# base_mcu_sch.net
KiCad netlist of a schematic drawn in EAGLE
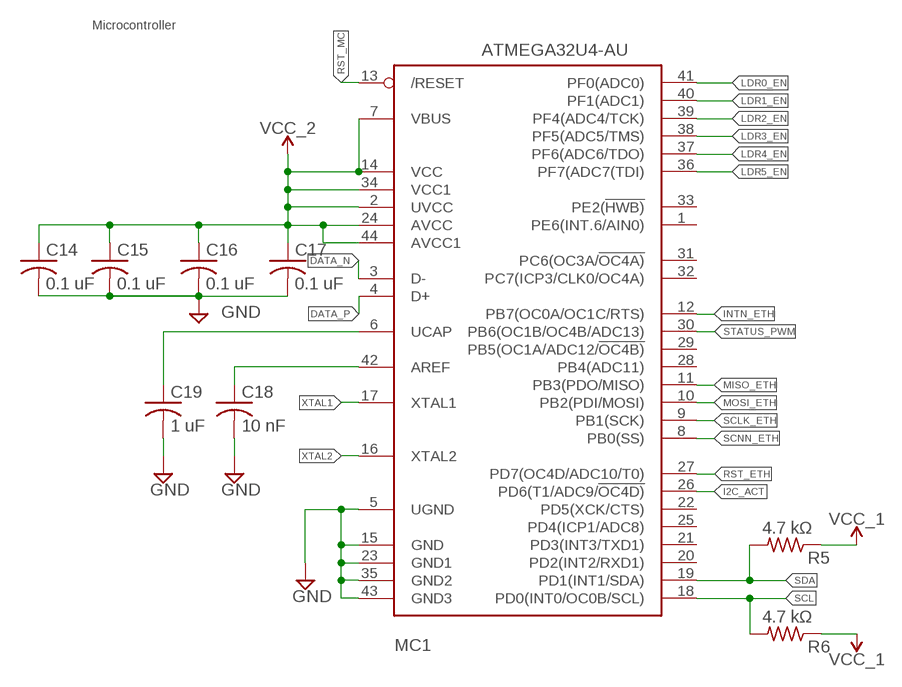
[diagram p0: schematic, sheet 1]

(export (version "E")
  (design (tool "Eeschema 10.0.6"))
  (components
    (comp (ref "C14")
      (value "0.1 uF")
      (footprint "eagle-import:C0603")
      (libsource (lib "eagle-import") (part "C-USC0603"))
    )
    (comp (ref "C15")
      (value "0.1 uF")
      (footprint "eagle-import:C0603")
      (libsource (lib "eagle-import") (part "C-USC0603"))
    )
    (comp (ref "C16")
      (value "0.1 uF")
      (footprint "eagle-import:C0603")
      (libsource (lib "eagle-import") (part "C-USC0603"))
    )
    (comp (ref "C17")
      (value "0.1 uF")
      (footprint "eagle-import:C0603")
      (libsource (lib "eagle-import") (part "C-USC0603"))
    )
    (comp (ref "C18")
      (value "10 nF")
      (footprint "eagle-import:C0603")
      (libsource (lib "eagle-import") (part "C-USC0603"))
    )
    (comp (ref "C19")
      (value "1 uF")
      (footprint "eagle-import:C0603")
      (libsource (lib "eagle-import") (part "C-USC0603"))
    )
    (comp (ref "MC1")
      (value "ATMEGA32U4-AU")
      (footprint "eagle-import:TQFP44")
      (libsource (lib "eagle-import") (part "ATMEGA32U4-AU"))
    )
    (comp (ref "R5")
      (value "4.7 kΩ")
      (footprint "eagle-import:R0603")
      (libsource (lib "eagle-import") (part "R-US_R0603"))
    )
    (comp (ref "R6")
      (value "4.7 kΩ")
      (footprint "eagle-import:R0603")
      (libsource (lib "eagle-import") (part "R-US_R0603"))
    )
  )
  (nets
    (net (code "1") (name "DATA_N") (class "Default")
      (node (ref "MC1") (pin "3") (pinfunction "D-_3") (pintype "bidirectional"))
    )
    (net (code "2") (name "DATA_P") (class "Default")
      (node (ref "MC1") (pin "4") (pinfunction "D+_4") (pintype "bidirectional"))
    )
    (net (code "3") (name "GND") (class "Default")
      (node (ref "C14") (pin "2") (pinfunction "2_2") (pintype "passive"))
      (node (ref "C15") (pin "2") (pinfunction "2_2") (pintype "passive"))
      (node (ref "C16") (pin "2") (pinfunction "2_2") (pintype "passive"))
      (node (ref "C17") (pin "2") (pinfunction "2_2") (pintype "passive"))
      (node (ref "C18") (pin "2") (pinfunction "2_2") (pintype "passive"))
      (node (ref "C19") (pin "2") (pinfunction "2_2") (pintype "passive"))
      (node (ref "MC1") (pin "15") (pinfunction "GND_15") (pintype "bidirectional"))
      (node (ref "MC1") (pin "23") (pinfunction "GND1_23") (pintype "bidirectional"))
      (node (ref "MC1") (pin "35") (pinfunction "GND2_35") (pintype "bidirectional"))
      (node (ref "MC1") (pin "43") (pinfunction "GND3_43") (pintype "bidirectional"))
      (node (ref "MC1") (pin "5") (pinfunction "UGND_5") (pintype "bidirectional"))
    )
    (net (code "4") (name "I2C_ACT") (class "Default")
      (node (ref "MC1") (pin "26") (pinfunction "PD6(T1/ADC9/~{OC4D})_26") (pintype "bidirectional"))
    )
    (net (code "5") (name "INTN_ETH") (class "Default")
      (node (ref "MC1") (pin "12") (pinfunction "PB7(OC0A/OC1C/RTS)_12") (pintype "bidirectional"))
    )
    (net (code "6") (name "LDR0_EN") (class "Default")
      (node (ref "MC1") (pin "41") (pinfunction "PF0(ADC0)_41") (pintype "bidirectional"))
    )
    (net (code "7") (name "LDR1_EN") (class "Default")
      (node (ref "MC1") (pin "40") (pinfunction "PF1(ADC1)_40") (pintype "bidirectional"))
    )
    (net (code "8") (name "LDR2_EN") (class "Default")
      (node (ref "MC1") (pin "39") (pinfunction "PF4(ADC4/TCK)_39") (pintype "bidirectional"))
    )
    (net (code "9") (name "LDR3_EN") (class "Default")
      (node (ref "MC1") (pin "38") (pinfunction "PF5(ADC5/TMS)_38") (pintype "bidirectional"))
    )
    (net (code "10") (name "LDR4_EN") (class "Default")
      (node (ref "MC1") (pin "37") (pinfunction "PF6(ADC6/TDO)_37") (pintype "bidirectional"))
    )
    (net (code "11") (name "LDR5_EN") (class "Default")
      (node (ref "MC1") (pin "36") (pinfunction "PF7(ADC7(TDI)_36") (pintype "bidirectional"))
    )
    (net (code "12") (name "MISO_ETH") (class "Default")
      (node (ref "MC1") (pin "11") (pinfunction "PB3(PDO/MISO)_11") (pintype "bidirectional"))
    )
    (net (code "13") (name "MOSI_ETH") (class "Default")
      (node (ref "MC1") (pin "10") (pinfunction "PB2(PDI/MOSI)_10") (pintype "bidirectional"))
    )
    (net (code "14") (name "Net-(MC1-AREF)") (class "Default")
      (node (ref "C18") (pin "1") (pinfunction "1_1") (pintype "passive"))
      (node (ref "MC1") (pin "42") (pinfunction "AREF_42") (pintype "bidirectional"))
    )
    (net (code "15") (name "Net-(MC1-UCAP)") (class "Default")
      (node (ref "C19") (pin "1") (pinfunction "1_1") (pintype "passive"))
      (node (ref "MC1") (pin "6") (pinfunction "UCAP_6") (pintype "bidirectional"))
    )
    (net (code "16") (name "RST_ETH") (class "Default")
      (node (ref "MC1") (pin "27") (pinfunction "PD7(OC4D/ADC10/T0)_27") (pintype "bidirectional"))
    )
    (net (code "17") (name "RST_MC") (class "Default")
      (node (ref "MC1") (pin "13") (pinfunction "/RESET_13") (pintype "bidirectional"))
    )
    (net (code "18") (name "SCL") (class "Default")
      (node (ref "MC1") (pin "18") (pinfunction "PD0(INT0/OC0B/SCL)_18") (pintype "bidirectional"))
      (node (ref "R6") (pin "2") (pinfunction "2_2") (pintype "passive"))
    )
    (net (code "19") (name "SCLK_ETH") (class "Default")
      (node (ref "MC1") (pin "9") (pinfunction "PB1(SCK)_9") (pintype "bidirectional"))
    )
    (net (code "20") (name "SCNN_ETH") (class "Default")
      (node (ref "MC1") (pin "8") (pinfunction "PB0(SS)_8") (pintype "bidirectional"))
    )
    (net (code "21") (name "SDA") (class "Default")
      (node (ref "MC1") (pin "19") (pinfunction "PD1(INT1/SDA)_19") (pintype "bidirectional"))
      (node (ref "R5") (pin "2") (pinfunction "2_2") (pintype "passive"))
    )
    (net (code "22") (name "STATUS_PWM") (class "Default")
      (node (ref "MC1") (pin "30") (pinfunction "PB6(OC1B/OC4B/ADC13)_30") (pintype "bidirectional"))
    )
    (net (code "23") (name "VCC_1") (class "Default")
      (node (ref "R5") (pin "1") (pinfunction "1_1") (pintype "passive"))
      (node (ref "R6") (pin "1") (pinfunction "1_1") (pintype "passive"))
    )
    (net (code "24") (name "VCC_2") (class "Default")
      (node (ref "C14") (pin "1") (pinfunction "1_1") (pintype "passive"))
      (node (ref "C15") (pin "1") (pinfunction "1_1") (pintype "passive"))
      (node (ref "C16") (pin "1") (pinfunction "1_1") (pintype "passive"))
      (node (ref "C17") (pin "1") (pinfunction "1_1") (pintype "passive"))
      (node (ref "MC1") (pin "14") (pinfunction "VCC_14") (pintype "bidirectional"))
      (node (ref "MC1") (pin "2") (pinfunction "UVCC_2") (pintype "bidirectional"))
      (node (ref "MC1") (pin "24") (pinfunction "AVCC_24") (pintype "bidirectional"))
      (node (ref "MC1") (pin "34") (pinfunction "VCC1_34") (pintype "bidirectional"))
      (node (ref "MC1") (pin "44") (pinfunction "AVCC1_44") (pintype "bidirectional"))
      (node (ref "MC1") (pin "7") (pinfunction "VBUS_7") (pintype "bidirectional"))
    )
    (net (code "25") (name "XTAL1") (class "Default")
      (node (ref "MC1") (pin "17") (pinfunction "XTAL1_17") (pintype "bidirectional"))
    )
    (net (code "26") (name "XTAL2") (class "Default")
      (node (ref "MC1") (pin "16") (pinfunction "XTAL2_16") (pintype "bidirectional"))
    )
    (net (code "27") (name "unconnected-(MC1-PB4(ADC11)-Pad28)") (class "Default")
      (node (ref "MC1") (pin "28") (pinfunction "PB4(ADC11)_28") (pintype "bidirectional"))
    )
    (net (code "28") (name "unconnected-(MC1-PB5(OC1A{slash}ADC12{slash}~{OC4B})-Pad29)") (class "Default")
      (node (ref "MC1") (pin "29") (pinfunction "PB5(OC1A/ADC12/~{OC4B})_29") (pintype "bidirectional"))
    )
    (net (code "29") (name "unconnected-(MC1-PC6(OC3A{slash}~{OC4A})-Pad31)") (class "Default")
      (node (ref "MC1") (pin "31") (pinfunction "PC6(OC3A/~{OC4A})_31") (pintype "bidirectional"))
    )
    (net (code "30") (name "unconnected-(MC1-PC7(ICP3{slash}CLK0{slash}OC4A)-Pad32)") (class "Default")
      (node (ref "MC1") (pin "32") (pinfunction "PC7(ICP3/CLK0/OC4A)_32") (pintype "bidirectional"))
    )
    (net (code "31") (name "unconnected-(MC1-PD2(INT2{slash}RXD1)-Pad20)") (class "Default")
      (node (ref "MC1") (pin "20") (pinfunction "PD2(INT2/RXD1)_20") (pintype "bidirectional"))
    )
    (net (code "32") (name "unconnected-(MC1-PD3(INT3{slash}TXD1)-Pad21)") (class "Default")
      (node (ref "MC1") (pin "21") (pinfunction "PD3(INT3/TXD1)_21") (pintype "bidirectional"))
    )
    (net (code "33") (name "unconnected-(MC1-PD4(ICP1{slash}ADC8)-Pad25)") (class "Default")
      (node (ref "MC1") (pin "25") (pinfunction "PD4(ICP1/ADC8)_25") (pintype "bidirectional"))
    )
    (net (code "34") (name "unconnected-(MC1-PD5(XCK{slash}CTS)-Pad22)") (class "Default")
      (node (ref "MC1") (pin "22") (pinfunction "PD5(XCK/CTS)_22") (pintype "bidirectional"))
    )
    (net (code "35") (name "unconnected-(MC1-PE2(~{HWB})-Pad33)") (class "Default")
      (node (ref "MC1") (pin "33") (pinfunction "PE2(~{HWB})_33") (pintype "bidirectional"))
    )
    (net (code "36") (name "unconnected-(MC1-PE6(INT.6{slash}AIN0)-Pad1)") (class "Default")
      (node (ref "MC1") (pin "1") (pinfunction "PE6(INT.6/AIN0)_1") (pintype "bidirectional"))
    )
  )
)
